# RoverWing-cover.net
KiCad netlist of a schematic drawn in EAGLE
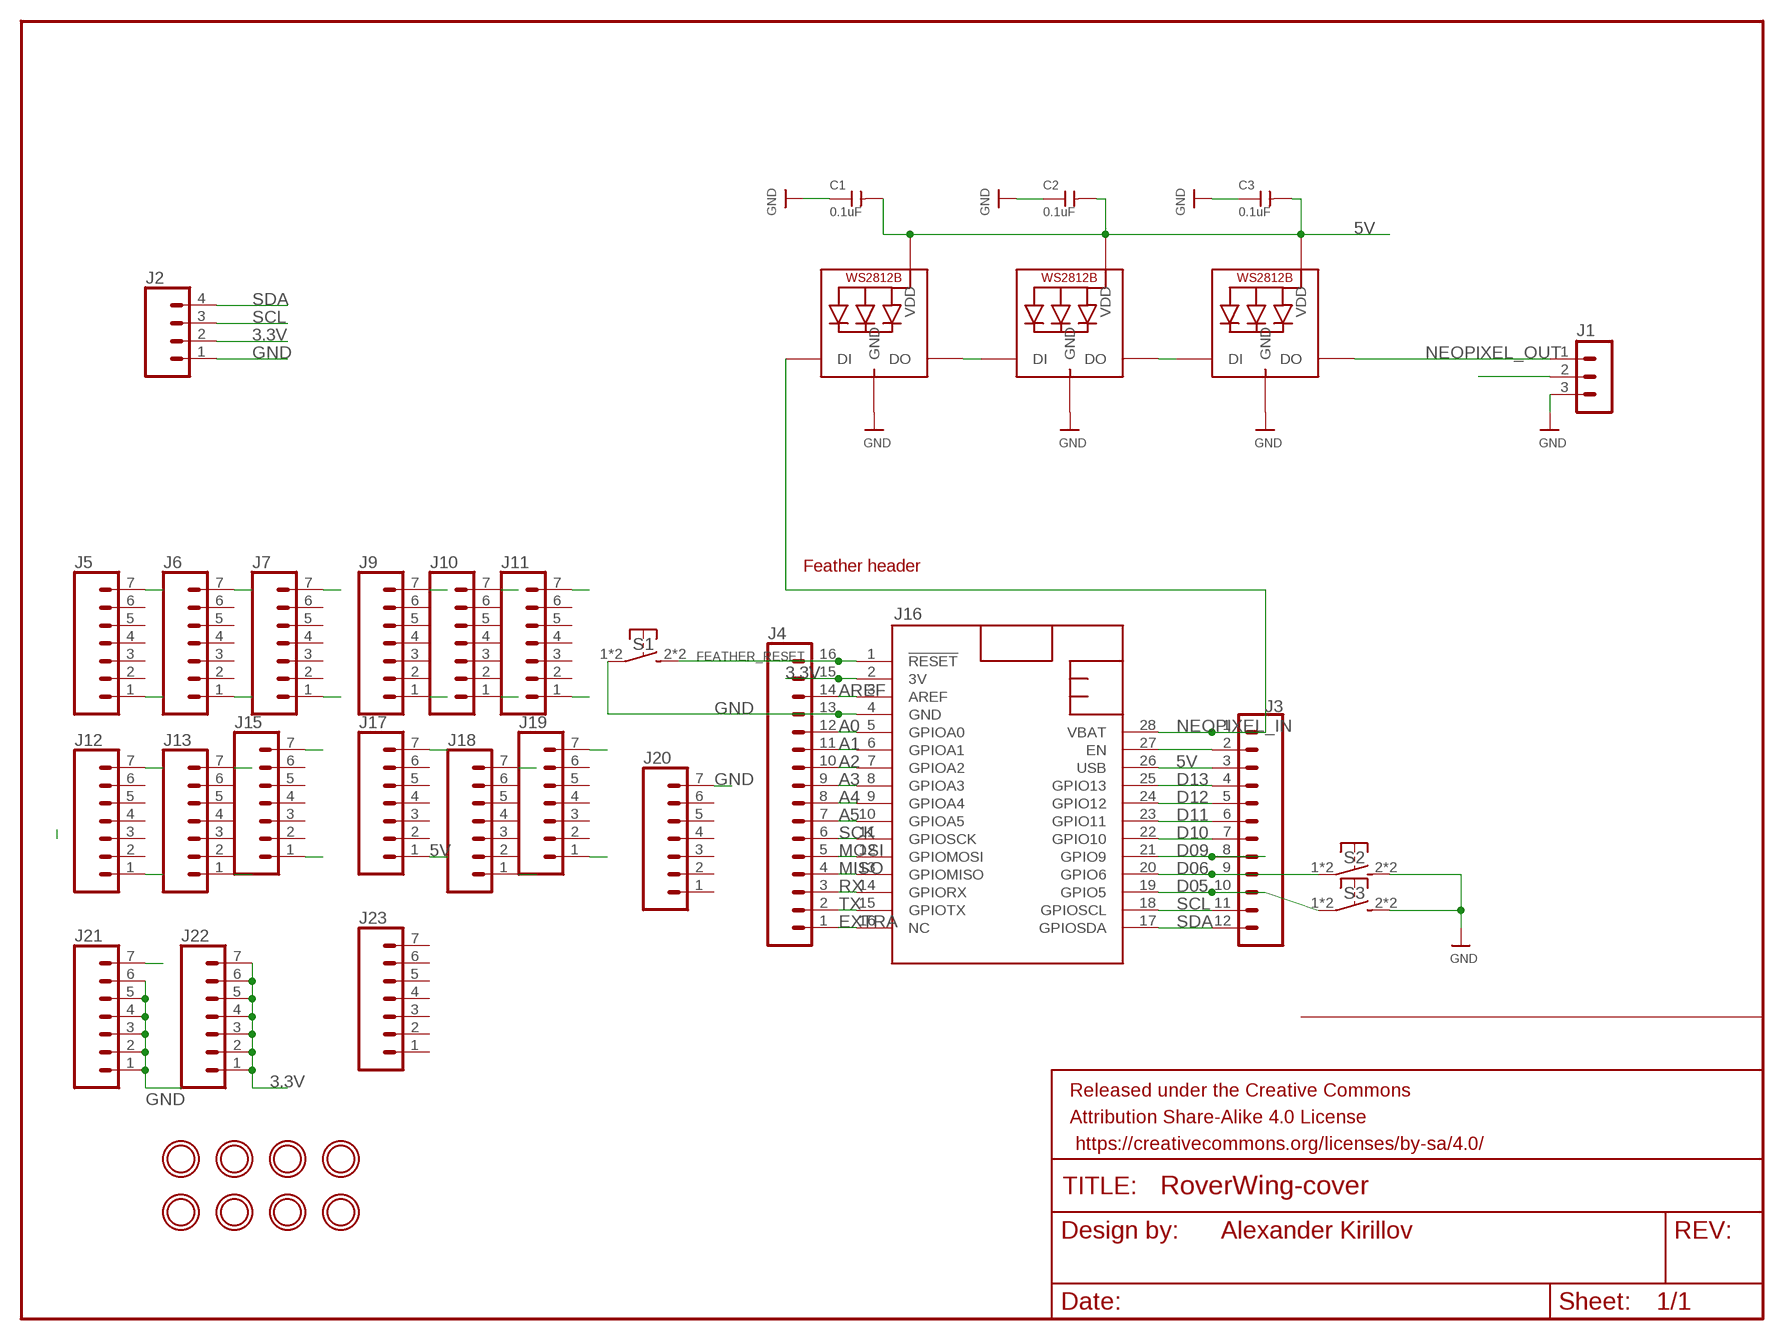
[diagram p0: schematic, sheet 1]

(export (version "E")
  (design (tool "Eeschema 10.0.6"))
  (components
    (comp (ref "C1")
      (value "0.1uF")
      (footprint "eagle-import:C0805")
      (libsource (lib "eagle-import") (part "CAP-CERAMIC-SMD-0805"))
    )
    (comp (ref "C2")
      (value "0.1uF")
      (footprint "eagle-import:C0805")
      (libsource (lib "eagle-import") (part "CAP-CERAMIC-SMD-0805"))
    )
    (comp (ref "C3")
      (value "0.1uF")
      (footprint "eagle-import:C0805")
      (libsource (lib "eagle-import") (part "CAP-CERAMIC-SMD-0805"))
    )
    (comp (ref "FRAME2")
      (value "FRAME-LETTERNO_PACKAGE")
      (footprint "eagle-import:DUMMY")
      (fields (field (name "DESIGNER") "Nobody"))
      (libsource (lib "eagle-import") (part "FRAME-LETTERNO_PACKAGE"))
    )
    (comp (ref "J1")
      (value "HEADER-PH-3P")
      (footprint "eagle-import:B3B-PH-K")
      (fields (field (name "PARTNO") "B3B-PH-K-S(LF)(SN)"))
      (libsource (lib "eagle-import") (part "HEADER-PH-3P"))
    )
    (comp (ref "J2")
      (value "CONN_04")
      (footprint "eagle-import:1X04")
      (libsource (lib "eagle-import") (part "CONN_04"))
    )
    (comp (ref "J3")
      (value "CONN_12NO_SILK")
      (footprint "eagle-import:1X12_NO_SILK")
      (libsource (lib "eagle-import") (part "CONN_12NO_SILK"))
    )
    (comp (ref "J4")
      (value "CONN_161X16_NO_SILK")
      (footprint "eagle-import:1X16_NO_SILK")
      (libsource (lib "eagle-import") (part "CONN_161X16_NO_SILK"))
    )
    (comp (ref "J5")
      (value "CONN_07NO_SILK")
      (footprint "eagle-import:1X07_NO_SILK")
      (libsource (lib "eagle-import") (part "CONN_07NO_SILK"))
    )
    (comp (ref "J6")
      (value "CONN_07NO_SILK")
      (footprint "eagle-import:1X07_NO_SILK")
      (libsource (lib "eagle-import") (part "CONN_07NO_SILK"))
    )
    (comp (ref "J7")
      (value "CONN_07NO_SILK")
      (footprint "eagle-import:1X07_NO_SILK")
      (libsource (lib "eagle-import") (part "CONN_07NO_SILK"))
    )
    (comp (ref "J9")
      (value "CONN_07NO_SILK")
      (footprint "eagle-import:1X07_NO_SILK")
      (libsource (lib "eagle-import") (part "CONN_07NO_SILK"))
    )
    (comp (ref "J10")
      (value "CONN_07NO_SILK")
      (footprint "eagle-import:1X07_NO_SILK")
      (libsource (lib "eagle-import") (part "CONN_07NO_SILK"))
    )
    (comp (ref "J11")
      (value "CONN_07NO_SILK")
      (footprint "eagle-import:1X07_NO_SILK")
      (libsource (lib "eagle-import") (part "CONN_07NO_SILK"))
    )
    (comp (ref "J12")
      (value "CONN_07NO_SILK")
      (footprint "eagle-import:1X07_NO_SILK")
      (libsource (lib "eagle-import") (part "CONN_07NO_SILK"))
    )
    (comp (ref "J13")
      (value "CONN_07NO_SILK")
      (footprint "eagle-import:1X07_NO_SILK")
      (libsource (lib "eagle-import") (part "CONN_07NO_SILK"))
    )
    (comp (ref "J15")
      (value "CONN_07NO_SILK")
      (footprint "eagle-import:1X07_NO_SILK")
      (libsource (lib "eagle-import") (part "CONN_07NO_SILK"))
    )
    (comp (ref "J16")
      (value "FEATHERWING_NODIM")
      (footprint "eagle-import:FEATHERWING_DIM")
      (libsource (lib "eagle-import") (part "FEATHERWING_NODIM"))
    )
    (comp (ref "J17")
      (value "CONN_07NO_SILK")
      (footprint "eagle-import:1X07_NO_SILK")
      (libsource (lib "eagle-import") (part "CONN_07NO_SILK"))
    )
    (comp (ref "J18")
      (value "CONN_07NO_SILK")
      (footprint "eagle-import:1X07_NO_SILK")
      (libsource (lib "eagle-import") (part "CONN_07NO_SILK"))
    )
    (comp (ref "J19")
      (value "CONN_07NO_SILK")
      (footprint "eagle-import:1X07_NO_SILK")
      (libsource (lib "eagle-import") (part "CONN_07NO_SILK"))
    )
    (comp (ref "J20")
      (value "CONN_07NO_SILK")
      (footprint "eagle-import:1X07_NO_SILK")
      (libsource (lib "eagle-import") (part "CONN_07NO_SILK"))
    )
    (comp (ref "J21")
      (value "CONN_07NO_SILK")
      (footprint "eagle-import:1X07_NO_SILK")
      (libsource (lib "eagle-import") (part "CONN_07NO_SILK"))
    )
    (comp (ref "J22")
      (value "CONN_07NO_SILK")
      (footprint "eagle-import:1X07_NO_SILK")
      (libsource (lib "eagle-import") (part "CONN_07NO_SILK"))
    )
    (comp (ref "J23")
      (value "CONN_07NO_SILK")
      (footprint "eagle-import:1X07_NO_SILK")
      (libsource (lib "eagle-import") (part "CONN_07NO_SILK"))
    )
    (comp (ref "LED1")
      (value "WS2812B5050")
      (footprint "eagle-import:WS2812B")
      (libsource (lib "eagle-import") (part "WS2812B5050"))
    )
    (comp (ref "LED2")
      (value "WS2812B5050")
      (footprint "eagle-import:WS2812B")
      (libsource (lib "eagle-import") (part "WS2812B5050"))
    )
    (comp (ref "LED3")
      (value "WS2812B5050")
      (footprint "eagle-import:WS2812B")
      (libsource (lib "eagle-import") (part "WS2812B5050"))
    )
    (comp (ref "S1")
      (value "SW-TACTILE-4.5X4.5_SMD")
      (footprint "eagle-import:TL3305")
      (libsource (lib "eagle-import") (part "SW-TACTILE-4.5X4.5_SMD"))
    )
    (comp (ref "S2")
      (value "SW-TACTILE-4.5X4.5_SMD")
      (footprint "eagle-import:TL3305")
      (libsource (lib "eagle-import") (part "SW-TACTILE-4.5X4.5_SMD"))
    )
    (comp (ref "S3")
      (value "SW-TACTILE-4.5X4.5_SMD")
      (footprint "eagle-import:TL3305")
      (libsource (lib "eagle-import") (part "SW-TACTILE-4.5X4.5_SMD"))
    )
    (comp (ref "U$3")
      (value "MOUNTINGHOLE3.0_NPH")
      (footprint "eagle-import:MOUNTINGHOLE_3.0_NPH")
      (libsource (lib "eagle-import") (part "MOUNTINGHOLE3.0_NPH"))
    )
    (comp (ref "U$4")
      (value "MOUNTINGHOLE3.0_NPH")
      (footprint "eagle-import:MOUNTINGHOLE_3.0_NPH")
      (libsource (lib "eagle-import") (part "MOUNTINGHOLE3.0_NPH"))
    )
    (comp (ref "U$14")
      (value "MOUNTINGHOLE3.0_NPH")
      (footprint "eagle-import:MOUNTINGHOLE_3.0_NPH")
      (libsource (lib "eagle-import") (part "MOUNTINGHOLE3.0_NPH"))
    )
    (comp (ref "U$15")
      (value "MOUNTINGHOLE3.0_NPH")
      (footprint "eagle-import:MOUNTINGHOLE_3.0_NPH")
      (libsource (lib "eagle-import") (part "MOUNTINGHOLE3.0_NPH"))
    )
    (comp (ref "U$24")
      (value "MOUNTINGHOLE3.0_NPH")
      (footprint "eagle-import:MOUNTINGHOLE_3.0_NPH")
      (libsource (lib "eagle-import") (part "MOUNTINGHOLE3.0_NPH"))
    )
    (comp (ref "U$25")
      (value "MOUNTINGHOLE3.0_NPH")
      (footprint "eagle-import:MOUNTINGHOLE_3.0_NPH")
      (libsource (lib "eagle-import") (part "MOUNTINGHOLE3.0_NPH"))
    )
    (comp (ref "U$26")
      (value "MOUNTINGHOLE3.0_NPH")
      (footprint "eagle-import:MOUNTINGHOLE_3.0_NPH")
      (libsource (lib "eagle-import") (part "MOUNTINGHOLE3.0_NPH"))
    )
    (comp (ref "U$27")
      (value "MOUNTINGHOLE3.0_NPH")
      (footprint "eagle-import:MOUNTINGHOLE_3.0_NPH")
      (libsource (lib "eagle-import") (part "MOUNTINGHOLE3.0_NPH"))
    )
  )
  (nets
    (net (code "1") (name "/3.3V") (class "Default")
      (node (ref "J16") (pin "2") (pinfunction "3V_2") (pintype "power_in"))
      (node (ref "J2") (pin "2") (pinfunction "2_2") (pintype "passive"))
      (node (ref "J22") (pin "1") (pinfunction "1_1") (pintype "passive"))
      (node (ref "J22") (pin "2") (pinfunction "2_2") (pintype "passive"))
      (node (ref "J22") (pin "3") (pinfunction "3_3") (pintype "passive"))
      (node (ref "J22") (pin "4") (pinfunction "4_4") (pintype "passive"))
      (node (ref "J22") (pin "5") (pinfunction "5_5") (pintype "passive"))
      (node (ref "J22") (pin "6") (pinfunction "6_6") (pintype "passive"))
      (node (ref "J22") (pin "7") (pinfunction "7_7") (pintype "passive"))
      (node (ref "J4") (pin "15") (pinfunction "15_15") (pintype "passive"))
    )
    (net (code "2") (name "/5V") (class "Default")
      (node (ref "C1") (pin "2") (pinfunction "2_2") (pintype "passive"))
      (node (ref "C2") (pin "2") (pinfunction "2_2") (pintype "passive"))
      (node (ref "C3") (pin "2") (pinfunction "2_2") (pintype "passive"))
      (node (ref "J1") (pin "2") (pinfunction "2_2") (pintype "passive"))
      (node (ref "J16") (pin "26") (pinfunction "USB_26") (pintype "power_in"))
      (node (ref "J17") (pin "1") (pinfunction "1_1") (pintype "passive"))
      (node (ref "J3") (pin "3") (pinfunction "3_3") (pintype "passive"))
      (node (ref "LED1") (pin "1-VDD") (pinfunction "VDD_1-VDD") (pintype "power_in"))
      (node (ref "LED2") (pin "1-VDD") (pinfunction "VDD_1-VDD") (pintype "power_in"))
      (node (ref "LED3") (pin "1-VDD") (pinfunction "VDD_1-VDD") (pintype "power_in"))
    )
    (net (code "3") (name "/A0") (class "Default")
      (node (ref "J16") (pin "5") (pinfunction "GPIOA0_5") (pintype "bidirectional"))
      (node (ref "J19") (pin "7") (pinfunction "7_7") (pintype "passive"))
      (node (ref "J4") (pin "12") (pinfunction "12_12") (pintype "passive"))
    )
    (net (code "4") (name "/A1") (class "Default")
      (node (ref "J16") (pin "6") (pinfunction "GPIOA1_6") (pintype "bidirectional"))
      (node (ref "J18") (pin "7") (pinfunction "7_7") (pintype "passive"))
      (node (ref "J4") (pin "11") (pinfunction "11_11") (pintype "passive"))
    )
    (net (code "5") (name "/A2") (class "Default")
      (node (ref "J16") (pin "7") (pinfunction "GPIOA2_7") (pintype "bidirectional"))
      (node (ref "J17") (pin "7") (pinfunction "7_7") (pintype "passive"))
      (node (ref "J4") (pin "10") (pinfunction "10_10") (pintype "passive"))
    )
    (net (code "6") (name "/A3") (class "Default")
      (node (ref "J15") (pin "7") (pinfunction "7_7") (pintype "passive"))
      (node (ref "J16") (pin "8") (pinfunction "GPIOA3_8") (pintype "bidirectional"))
      (node (ref "J4") (pin "9") (pinfunction "9_9") (pintype "passive"))
    )
    (net (code "7") (name "/A4") (class "Default")
      (node (ref "J13") (pin "7") (pinfunction "7_7") (pintype "passive"))
      (node (ref "J16") (pin "9") (pinfunction "GPIOA4_9") (pintype "bidirectional"))
      (node (ref "J4") (pin "8") (pinfunction "8_8") (pintype "passive"))
    )
    (net (code "8") (name "/A5") (class "Default")
      (node (ref "J12") (pin "7") (pinfunction "7_7") (pintype "passive"))
      (node (ref "J16") (pin "10") (pinfunction "GPIOA5_10") (pintype "bidirectional"))
      (node (ref "J4") (pin "7") (pinfunction "7_7") (pintype "passive"))
    )
    (net (code "9") (name "/AREF") (class "Default")
      (node (ref "J16") (pin "3") (pinfunction "AREF_3") (pintype "passive"))
      (node (ref "J21") (pin "7") (pinfunction "7_7") (pintype "passive"))
      (node (ref "J4") (pin "14") (pinfunction "14_14") (pintype "passive"))
    )
    (net (code "10") (name "/D05") (class "Default")
      (node (ref "J16") (pin "19") (pinfunction "GPIO5_19") (pintype "bidirectional"))
      (node (ref "J3") (pin "10") (pinfunction "10_10") (pintype "passive"))
      (node (ref "J7") (pin "1") (pinfunction "1_1") (pintype "passive"))
      (node (ref "S3") (pin "1") (pinfunction "P1_1") (pintype "passive"))
      (node (ref "S3") (pin "4") (pinfunction "P1_4") (pintype "passive"))
    )
    (net (code "11") (name "/D06") (class "Default")
      (node (ref "J16") (pin "20") (pinfunction "GPIO6_20") (pintype "bidirectional"))
      (node (ref "J3") (pin "9") (pinfunction "9_9") (pintype "passive"))
      (node (ref "J9") (pin "1") (pinfunction "1_1") (pintype "passive"))
      (node (ref "S2") (pin "1") (pinfunction "P1_1") (pintype "passive"))
      (node (ref "S2") (pin "4") (pinfunction "P1_4") (pintype "passive"))
    )
    (net (code "12") (name "/D09") (class "Default")
      (node (ref "J10") (pin "1") (pinfunction "1_1") (pintype "passive"))
      (node (ref "J16") (pin "21") (pinfunction "GPIO9_21") (pintype "bidirectional"))
      (node (ref "J3") (pin "8") (pinfunction "8_8") (pintype "passive"))
    )
    (net (code "13") (name "/D10") (class "Default")
      (node (ref "J11") (pin "1") (pinfunction "1_1") (pintype "passive"))
      (node (ref "J16") (pin "22") (pinfunction "GPIO10_22") (pintype "bidirectional"))
      (node (ref "J3") (pin "7") (pinfunction "7_7") (pintype "passive"))
    )
    (net (code "14") (name "/D11") (class "Default")
      (node (ref "J12") (pin "1") (pinfunction "1_1") (pintype "passive"))
      (node (ref "J16") (pin "23") (pinfunction "GPIO11_23") (pintype "bidirectional"))
      (node (ref "J3") (pin "6") (pinfunction "6_6") (pintype "passive"))
    )
    (net (code "15") (name "/D12") (class "Default")
      (node (ref "J13") (pin "1") (pinfunction "1_1") (pintype "passive"))
      (node (ref "J16") (pin "24") (pinfunction "GPIO12_24") (pintype "bidirectional"))
      (node (ref "J3") (pin "5") (pinfunction "5_5") (pintype "passive"))
    )
    (net (code "16") (name "/D13") (class "Default")
      (node (ref "J15") (pin "1") (pinfunction "1_1") (pintype "passive"))
      (node (ref "J16") (pin "25") (pinfunction "GPIO13_25") (pintype "bidirectional"))
      (node (ref "J3") (pin "4") (pinfunction "4_4") (pintype "passive"))
    )
    (net (code "17") (name "/EXTRA") (class "Default")
      (node (ref "J16") (pin "16") (pinfunction "NC_16") (pintype "passive"))
      (node (ref "J4") (pin "1") (pinfunction "1_1") (pintype "passive"))
      (node (ref "J5") (pin "7") (pinfunction "7_7") (pintype "passive"))
    )
    (net (code "18") (name "/FEATHER_RESET") (class "Default")
      (node (ref "J16") (pin "1") (pinfunction "~{RESET}_1") (pintype "input"))
      (node (ref "J4") (pin "16") (pinfunction "16_16") (pintype "passive"))
      (node (ref "S1") (pin "2") (pinfunction "S1_2") (pintype "passive"))
      (node (ref "S1") (pin "3") (pinfunction "S1_3") (pintype "passive"))
    )
    (net (code "19") (name "/MISO") (class "Default")
      (node (ref "J16") (pin "13") (pinfunction "GPIOMISO_13") (pintype "bidirectional"))
      (node (ref "J4") (pin "4") (pinfunction "4_4") (pintype "passive"))
      (node (ref "J9") (pin "7") (pinfunction "7_7") (pintype "passive"))
    )
    (net (code "20") (name "/MOSI") (class "Default")
      (node (ref "J10") (pin "7") (pinfunction "7_7") (pintype "passive"))
      (node (ref "J16") (pin "12") (pinfunction "GPIOMOSI_12") (pintype "bidirectional"))
      (node (ref "J4") (pin "5") (pinfunction "5_5") (pintype "passive"))
    )
    (net (code "21") (name "/N$37") (class "Default")
      (node (ref "J16") (pin "27") (pinfunction "EN_27") (pintype "passive"))
      (node (ref "J18") (pin "1") (pinfunction "1_1") (pintype "passive"))
      (node (ref "J3") (pin "2") (pinfunction "2_2") (pintype "passive"))
    )
    (net (code "22") (name "/NEOPIXEL_IN") (class "Default")
      (node (ref "J16") (pin "28") (pinfunction "VBAT_28") (pintype "power_in"))
      (node (ref "J3") (pin "1") (pinfunction "1_1") (pintype "passive"))
      (node (ref "LED1") (pin "4-DIN") (pinfunction "DI_4-DIN") (pintype "input"))
    )
    (net (code "23") (name "/NEOPIXEL_OUT") (class "Default")
      (node (ref "J1") (pin "1") (pinfunction "1_1") (pintype "passive"))
      (node (ref "LED3") (pin "2-DOUT") (pinfunction "DO_2-DOUT") (pintype "output"))
    )
    (net (code "24") (name "/RX") (class "Default")
      (node (ref "J16") (pin "14") (pinfunction "GPIORX_14") (pintype "bidirectional"))
      (node (ref "J4") (pin "3") (pinfunction "3_3") (pintype "passive"))
      (node (ref "J7") (pin "7") (pinfunction "7_7") (pintype "passive"))
    )
    (net (code "25") (name "/SCK") (class "Default")
      (node (ref "J11") (pin "7") (pinfunction "7_7") (pintype "passive"))
      (node (ref "J16") (pin "11") (pinfunction "GPIOSCK_11") (pintype "bidirectional"))
      (node (ref "J4") (pin "6") (pinfunction "6_6") (pintype "passive"))
    )
    (net (code "26") (name "/SCL") (class "Default")
      (node (ref "J16") (pin "18") (pinfunction "GPIOSCL_18") (pintype "bidirectional"))
      (node (ref "J2") (pin "3") (pinfunction "3_3") (pintype "passive"))
      (node (ref "J3") (pin "11") (pinfunction "11_11") (pintype "passive"))
      (node (ref "J6") (pin "1") (pinfunction "1_1") (pintype "passive"))
    )
    (net (code "27") (name "/SDA") (class "Default")
      (node (ref "J16") (pin "17") (pinfunction "GPIOSDA_17") (pintype "bidirectional"))
      (node (ref "J2") (pin "4") (pinfunction "4_4") (pintype "passive"))
      (node (ref "J3") (pin "12") (pinfunction "12_12") (pintype "passive"))
      (node (ref "J5") (pin "1") (pinfunction "1_1") (pintype "passive"))
    )
    (net (code "28") (name "/TX") (class "Default")
      (node (ref "J16") (pin "15") (pinfunction "GPIOTX_15") (pintype "bidirectional"))
      (node (ref "J4") (pin "2") (pinfunction "2_2") (pintype "passive"))
      (node (ref "J6") (pin "7") (pinfunction "7_7") (pintype "passive"))
    )
    (net (code "29") (name "GND") (class "Default")
      (node (ref "C1") (pin "1") (pinfunction "1_1") (pintype "passive"))
      (node (ref "C2") (pin "1") (pinfunction "1_1") (pintype "passive"))
      (node (ref "C3") (pin "1") (pinfunction "1_1") (pintype "passive"))
      (node (ref "J1") (pin "3") (pinfunction "3_3") (pintype "passive"))
      (node (ref "J16") (pin "4") (pinfunction "GND_4") (pintype "power_in"))
      (node (ref "J2") (pin "1") (pinfunction "1_1") (pintype "passive"))
      (node (ref "J20") (pin "7") (pinfunction "7_7") (pintype "passive"))
      (node (ref "J21") (pin "1") (pinfunction "1_1") (pintype "passive"))
      (node (ref "J21") (pin "2") (pinfunction "2_2") (pintype "passive"))
      (node (ref "J21") (pin "3") (pinfunction "3_3") (pintype "passive"))
      (node (ref "J21") (pin "4") (pinfunction "4_4") (pintype "passive"))
      (node (ref "J21") (pin "5") (pinfunction "5_5") (pintype "passive"))
      (node (ref "J21") (pin "6") (pinfunction "6_6") (pintype "passive"))
      (node (ref "J4") (pin "13") (pinfunction "13_13") (pintype "passive"))
      (node (ref "LED1") (pin "3-GND") (pinfunction "GND_3-GND") (pintype "power_in"))
      (node (ref "LED2") (pin "3-GND") (pinfunction "GND_3-GND") (pintype "power_in"))
      (node (ref "LED3") (pin "3-GND") (pinfunction "GND_3-GND") (pintype "power_in"))
      (node (ref "S1") (pin "1") (pinfunction "P1_1") (pintype "passive"))
      (node (ref "S1") (pin "4") (pinfunction "P1_4") (pintype "passive"))
      (node (ref "S2") (pin "2") (pinfunction "S1_2") (pintype "passive"))
      (node (ref "S2") (pin "3") (pinfunction "S1_3") (pintype "passive"))
      (node (ref "S3") (pin "2") (pinfunction "S1_2") (pintype "passive"))
      (node (ref "S3") (pin "3") (pinfunction "S1_3") (pintype "passive"))
    )
    (net (code "30") (name "Net-(LED1-DO)") (class "Default")
      (node (ref "LED1") (pin "2-DOUT") (pinfunction "DO_2-DOUT") (pintype "output"))
      (node (ref "LED2") (pin "4-DIN") (pinfunction "DI_4-DIN") (pintype "input"))
    )
    (net (code "31") (name "Net-(LED2-DO)") (class "Default")
      (node (ref "LED2") (pin "2-DOUT") (pinfunction "DO_2-DOUT") (pintype "output"))
      (node (ref "LED3") (pin "4-DIN") (pinfunction "DI_4-DIN") (pintype "input"))
    )
    (net (code "32") (name "unconnected-(J5-Pad2)") (class "Default")
      (node (ref "J5") (pin "2") (pinfunction "2_2") (pintype "passive"))
    )
    (net (code "33") (name "unconnected-(J5-Pad3)") (class "Default")
      (node (ref "J5") (pin "3") (pinfunction "3_3") (pintype "passive"))
    )
    (net (code "34") (name "unconnected-(J5-Pad4)") (class "Default")
      (node (ref "J5") (pin "4") (pinfunction "4_4") (pintype "passive"))
    )
    (net (code "35") (name "unconnected-(J5-Pad5)") (class "Default")
      (node (ref "J5") (pin "5") (pinfunction "5_5") (pintype "passive"))
    )
    (net (code "36") (name "unconnected-(J5-Pad6)") (class "Default")
      (node (ref "J5") (pin "6") (pinfunction "6_6") (pintype "passive"))
    )
    (net (code "37") (name "unconnected-(J6-Pad2)") (class "Default")
      (node (ref "J6") (pin "2") (pinfunction "2_2") (pintype "passive"))
    )
    (net (code "38") (name "unconnected-(J6-Pad3)") (class "Default")
      (node (ref "J6") (pin "3") (pinfunction "3_3") (pintype "passive"))
    )
    (net (code "39") (name "unconnected-(J6-Pad4)") (class "Default")
      (node (ref "J6") (pin "4") (pinfunction "4_4") (pintype "passive"))
    )
    (net (code "40") (name "unconnected-(J6-Pad5)") (class "Default")
      (node (ref "J6") (pin "5") (pinfunction "5_5") (pintype "passive"))
    )
    (net (code "41") (name "unconnected-(J6-Pad6)") (class "Default")
      (node (ref "J6") (pin "6") (pinfunction "6_6") (pintype "passive"))
    )
    (net (code "42") (name "unconnected-(J7-Pad2)") (class "Default")
      (node (ref "J7") (pin "2") (pinfunction "2_2") (pintype "passive"))
    )
    (net (code "43") (name "unconnected-(J7-Pad3)") (class "Default")
      (node (ref "J7") (pin "3") (pinfunction "3_3") (pintype "passive"))
    )
    (net (code "44") (name "unconnected-(J7-Pad4)") (class "Default")
      (node (ref "J7") (pin "4") (pinfunction "4_4") (pintype "passive"))
    )
    (net (code "45") (name "unconnected-(J7-Pad5)") (class "Default")
      (node (ref "J7") (pin "5") (pinfunction "5_5") (pintype "passive"))
    )
    (net (code "46") (name "unconnected-(J7-Pad6)") (class "Default")
      (node (ref "J7") (pin "6") (pinfunction "6_6") (pintype "passive"))
    )
    (net (code "47") (name "unconnected-(J9-Pad2)") (class "Default")
      (node (ref "J9") (pin "2") (pinfunction "2_2") (pintype "passive"))
    )
    (net (code "48") (name "unconnected-(J9-Pad3)") (class "Default")
      (node (ref "J9") (pin "3") (pinfunction "3_3") (pintype "passive"))
    )
    (net (code "49") (name "unconnected-(J9-Pad4)") (class "Default")
      (node (ref "J9") (pin "4") (pinfunction "4_4") (pintype "passive"))
    )
    (net (code "50") (name "unconnected-(J9-Pad5)") (class "Default")
      (node (ref "J9") (pin "5") (pinfunction "5_5") (pintype "passive"))
    )
    (net (code "51") (name "unconnected-(J9-Pad6)") (class "Default")
      (node (ref "J9") (pin "6") (pinfunction "6_6") (pintype "passive"))
    )
    (net (code "52") (name "unconnected-(J10-Pad2)") (class "Default")
      (node (ref "J10") (pin "2") (pinfunction "2_2") (pintype "passive"))
    )
    (net (code "53") (name "unconnected-(J10-Pad3)") (class "Default")
      (node (ref "J10") (pin "3") (pinfunction "3_3") (pintype "passive"))
    )
    (net (code "54") (name "unconnected-(J10-Pad4)") (class "Default")
      (node (ref "J10") (pin "4") (pinfunction "4_4") (pintype "passive"))
    )
    (net (code "55") (name "unconnected-(J10-Pad5)") (class "Default")
      (node (ref "J10") (pin "5") (pinfunction "5_5") (pintype "passive"))
    )
    (net (code "56") (name "unconnected-(J10-Pad6)") (class "Default")
      (node (ref "J10") (pin "6") (pinfunction "6_6") (pintype "passive"))
    )
    (net (code "57") (name "unconnected-(J11-Pad2)") (class "Default")
      (node (ref "J11") (pin "2") (pinfunction "2_2") (pintype "passive"))
    )
    (net (code "58") (name "unconnected-(J11-Pad3)") (class "Default")
      (node (ref "J11") (pin "3") (pinfunction "3_3") (pintype "passive"))
    )
    (net (code "59") (name "unconnected-(J11-Pad4)") (class "Default")
      (node (ref "J11") (pin "4") (pinfunction "4_4") (pintype "passive"))
    )
    (net (code "60") (name "unconnected-(J11-Pad5)") (class "Default")
      (node (ref "J11") (pin "5") (pinfunction "5_5") (pintype "passive"))
    )
    (net (code "61") (name "unconnected-(J11-Pad6)") (class "Default")
      (node (ref "J11") (pin "6") (pinfunction "6_6") (pintype "passive"))
    )
    (net (code "62") (name "unconnected-(J12-Pad2)") (class "Default")
      (node (ref "J12") (pin "2") (pinfunction "2_2") (pintype "passive"))
    )
    (net (code "63") (name "unconnected-(J12-Pad3)") (class "Default")
      (node (ref "J12") (pin "3") (pinfunction "3_3") (pintype "passive"))
    )
    (net (code "64") (name "unconnected-(J12-Pad4)") (class "Default")
      (node (ref "J12") (pin "4") (pinfunction "4_4") (pintype "passive"))
    )
    (net (code "65") (name "unconnected-(J12-Pad5)") (class "Default")
      (node (ref "J12") (pin "5") (pinfunction "5_5") (pintype "passive"))
    )
    (net (code "66") (name "unconnected-(J12-Pad6)") (class "Default")
      (node (ref "J12") (pin "6") (pinfunction "6_6") (pintype "passive"))
    )
    (net (code "67") (name "unconnected-(J13-Pad2)") (class "Default")
      (node (ref "J13") (pin "2") (pinfunction "2_2") (pintype "passive"))
    )
    (net (code "68") (name "unconnected-(J13-Pad3)") (class "Default")
      (node (ref "J13") (pin "3") (pinfunction "3_3") (pintype "passive"))
    )
    (net (code "69") (name "unconnected-(J13-Pad4)") (class "Default")
      (node (ref "J13") (pin "4") (pinfunction "4_4") (pintype "passive"))
    )
    (net (code "70") (name "unconnected-(J13-Pad5)") (class "Default")
      (node (ref "J13") (pin "5") (pinfunction "5_5") (pintype "passive"))
    )
    (net (code "71") (name "unconnected-(J13-Pad6)") (class "Default")
      (node (ref "J13") (pin "6") (pinfunction "6_6") (pintype "passive"))
    )
    (net (code "72") (name "unconnected-(J15-Pad2)") (class "Default")
      (node (ref "J15") (pin "2") (pinfunction "2_2") (pintype "passive"))
    )
    (net (code "73") (name "unconnected-(J15-Pad3)") (class "Default")
      (node (ref "J15") (pin "3") (pinfunction "3_3") (pintype "passive"))
    )
    (net (code "74") (name "unconnected-(J15-Pad4)") (class "Default")
      (node (ref "J15") (pin "4") (pinfunction "4_4") (pintype "passive"))
    )
    (net (code "75") (name "unconnected-(J15-Pad5)") (class "Default")
      (node (ref "J15") (pin "5") (pinfunction "5_5") (pintype "passive"))
    )
    (net (code "76") (name "unconnected-(J15-Pad6)") (class "Default")
      (node (ref "J15") (pin "6") (pinfunction "6_6") (pintype "passive"))
    )
    (net (code "77") (name "unconnected-(J17-Pad2)") (class "Default")
      (node (ref "J17") (pin "2") (pinfunction "2_2") (pintype "passive"))
    )
    (net (code "78") (name "unconnected-(J17-Pad3)") (class "Default")
      (node (ref "J17") (pin "3") (pinfunction "3_3") (pintype "passive"))
    )
    (net (code "79") (name "unconnected-(J17-Pad4)") (class "Default")
      (node (ref "J17") (pin "4") (pinfunction "4_4") (pintype "passive"))
    )
    (net (code "80") (name "unconnected-(J17-Pad5)") (class "Default")
      (node (ref "J17") (pin "5") (pinfunction "5_5") (pintype "passive"))
    )
    (net (code "81") (name "unconnected-(J17-Pad6)") (class "Default")
      (node (ref "J17") (pin "6") (pinfunction "6_6") (pintype "passive"))
    )
    (net (code "82") (name "unconnected-(J18-Pad2)") (class "Default")
      (node (ref "J18") (pin "2") (pinfunction "2_2") (pintype "passive"))
    )
    (net (code "83") (name "unconnected-(J18-Pad3)") (class "Default")
      (node (ref "J18") (pin "3") (pinfunction "3_3") (pintype "passive"))
    )
    (net (code "84") (name "unconnected-(J18-Pad4)") (class "Default")
      (node (ref "J18") (pin "4") (pinfunction "4_4") (pintype "passive"))
    )
    (net (code "85") (name "unconnected-(J18-Pad5)") (class "Default")
      (node (ref "J18") (pin "5") (pinfunction "5_5") (pintype "passive"))
    )
    (net (code "86") (name "unconnected-(J18-Pad6)") (class "Default")
      (node (ref "J18") (pin "6") (pinfunction "6_6") (pintype "passive"))
    )
    (net (code "87") (name "unconnected-(J19-Pad1)") (class "Default")
      (node (ref "J19") (pin "1") (pinfunction "1_1") (pintype "passive"))
    )
    (net (code "88") (name "unconnected-(J19-Pad2)") (class "Default")
      (node (ref "J19") (pin "2") (pinfunction "2_2") (pintype "passive"))
    )
    (net (code "89") (name "unconnected-(J19-Pad3)") (class "Default")
      (node (ref "J19") (pin "3") (pinfunction "3_3") (pintype "passive"))
    )
    (net (code "90") (name "unconnected-(J19-Pad4)") (class "Default")
      (node (ref "J19") (pin "4") (pinfunction "4_4") (pintype "passive"))
    )
    (net (code "91") (name "unconnected-(J19-Pad5)") (class "Default")
      (node (ref "J19") (pin "5") (pinfunction "5_5") (pintype "passive"))
    )
    (net (code "92") (name "unconnected-(J19-Pad6)") (class "Default")
      (node (ref "J19") (pin "6") (pinfunction "6_6") (pintype "passive"))
    )
    (net (code "93") (name "unconnected-(J20-Pad1)") (class "Default")
      (node (ref "J20") (pin "1") (pinfunction "1_1") (pintype "passive"))
    )
    (net (code "94") (name "unconnected-(J20-Pad2)") (class "Default")
      (node (ref "J20") (pin "2") (pinfunction "2_2") (pintype "passive"))
    )
    (net (code "95") (name "unconnected-(J20-Pad3)") (class "Default")
      (node (ref "J20") (pin "3") (pinfunction "3_3") (pintype "passive"))
    )
    (net (code "96") (name "unconnected-(J20-Pad4)") (class "Default")
      (node (ref "J20") (pin "4") (pinfunction "4_4") (pintype "passive"))
    )
    (net (code "97") (name "unconnected-(J20-Pad5)") (class "Default")
      (node (ref "J20") (pin "5") (pinfunction "5_5") (pintype "passive"))
    )
    (net (code "98") (name "unconnected-(J20-Pad6)") (class "Default")
      (node (ref "J20") (pin "6") (pinfunction "6_6") (pintype "passive"))
    )
    (net (code "99") (name "unconnected-(J23-Pad1)") (class "Default")
      (node (ref "J23") (pin "1") (pinfunction "1_1") (pintype "passive"))
    )
    (net (code "100") (name "unconnected-(J23-Pad2)") (class "Default")
      (node (ref "J23") (pin "2") (pinfunction "2_2") (pintype "passive"))
    )
    (net (code "101") (name "unconnected-(J23-Pad3)") (class "Default")
      (node (ref "J23") (pin "3") (pinfunction "3_3") (pintype "passive"))
    )
    (net (code "102") (name "unconnected-(J23-Pad4)") (class "Default")
      (node (ref "J23") (pin "4") (pinfunction "4_4") (pintype "passive"))
    )
    (net (code "103") (name "unconnected-(J23-Pad5)") (class "Default")
      (node (ref "J23") (pin "5") (pinfunction "5_5") (pintype "passive"))
    )
    (net (code "104") (name "unconnected-(J23-Pad6)") (class "Default")
      (node (ref "J23") (pin "6") (pinfunction "6_6") (pintype "passive"))
    )
    (net (code "105") (name "unconnected-(J23-Pad7)") (class "Default")
      (node (ref "J23") (pin "7") (pinfunction "7_7") (pintype "passive"))
    )
  )
)
